# IO.net
KiCad netlist of a schematic drawn in Altium Designer
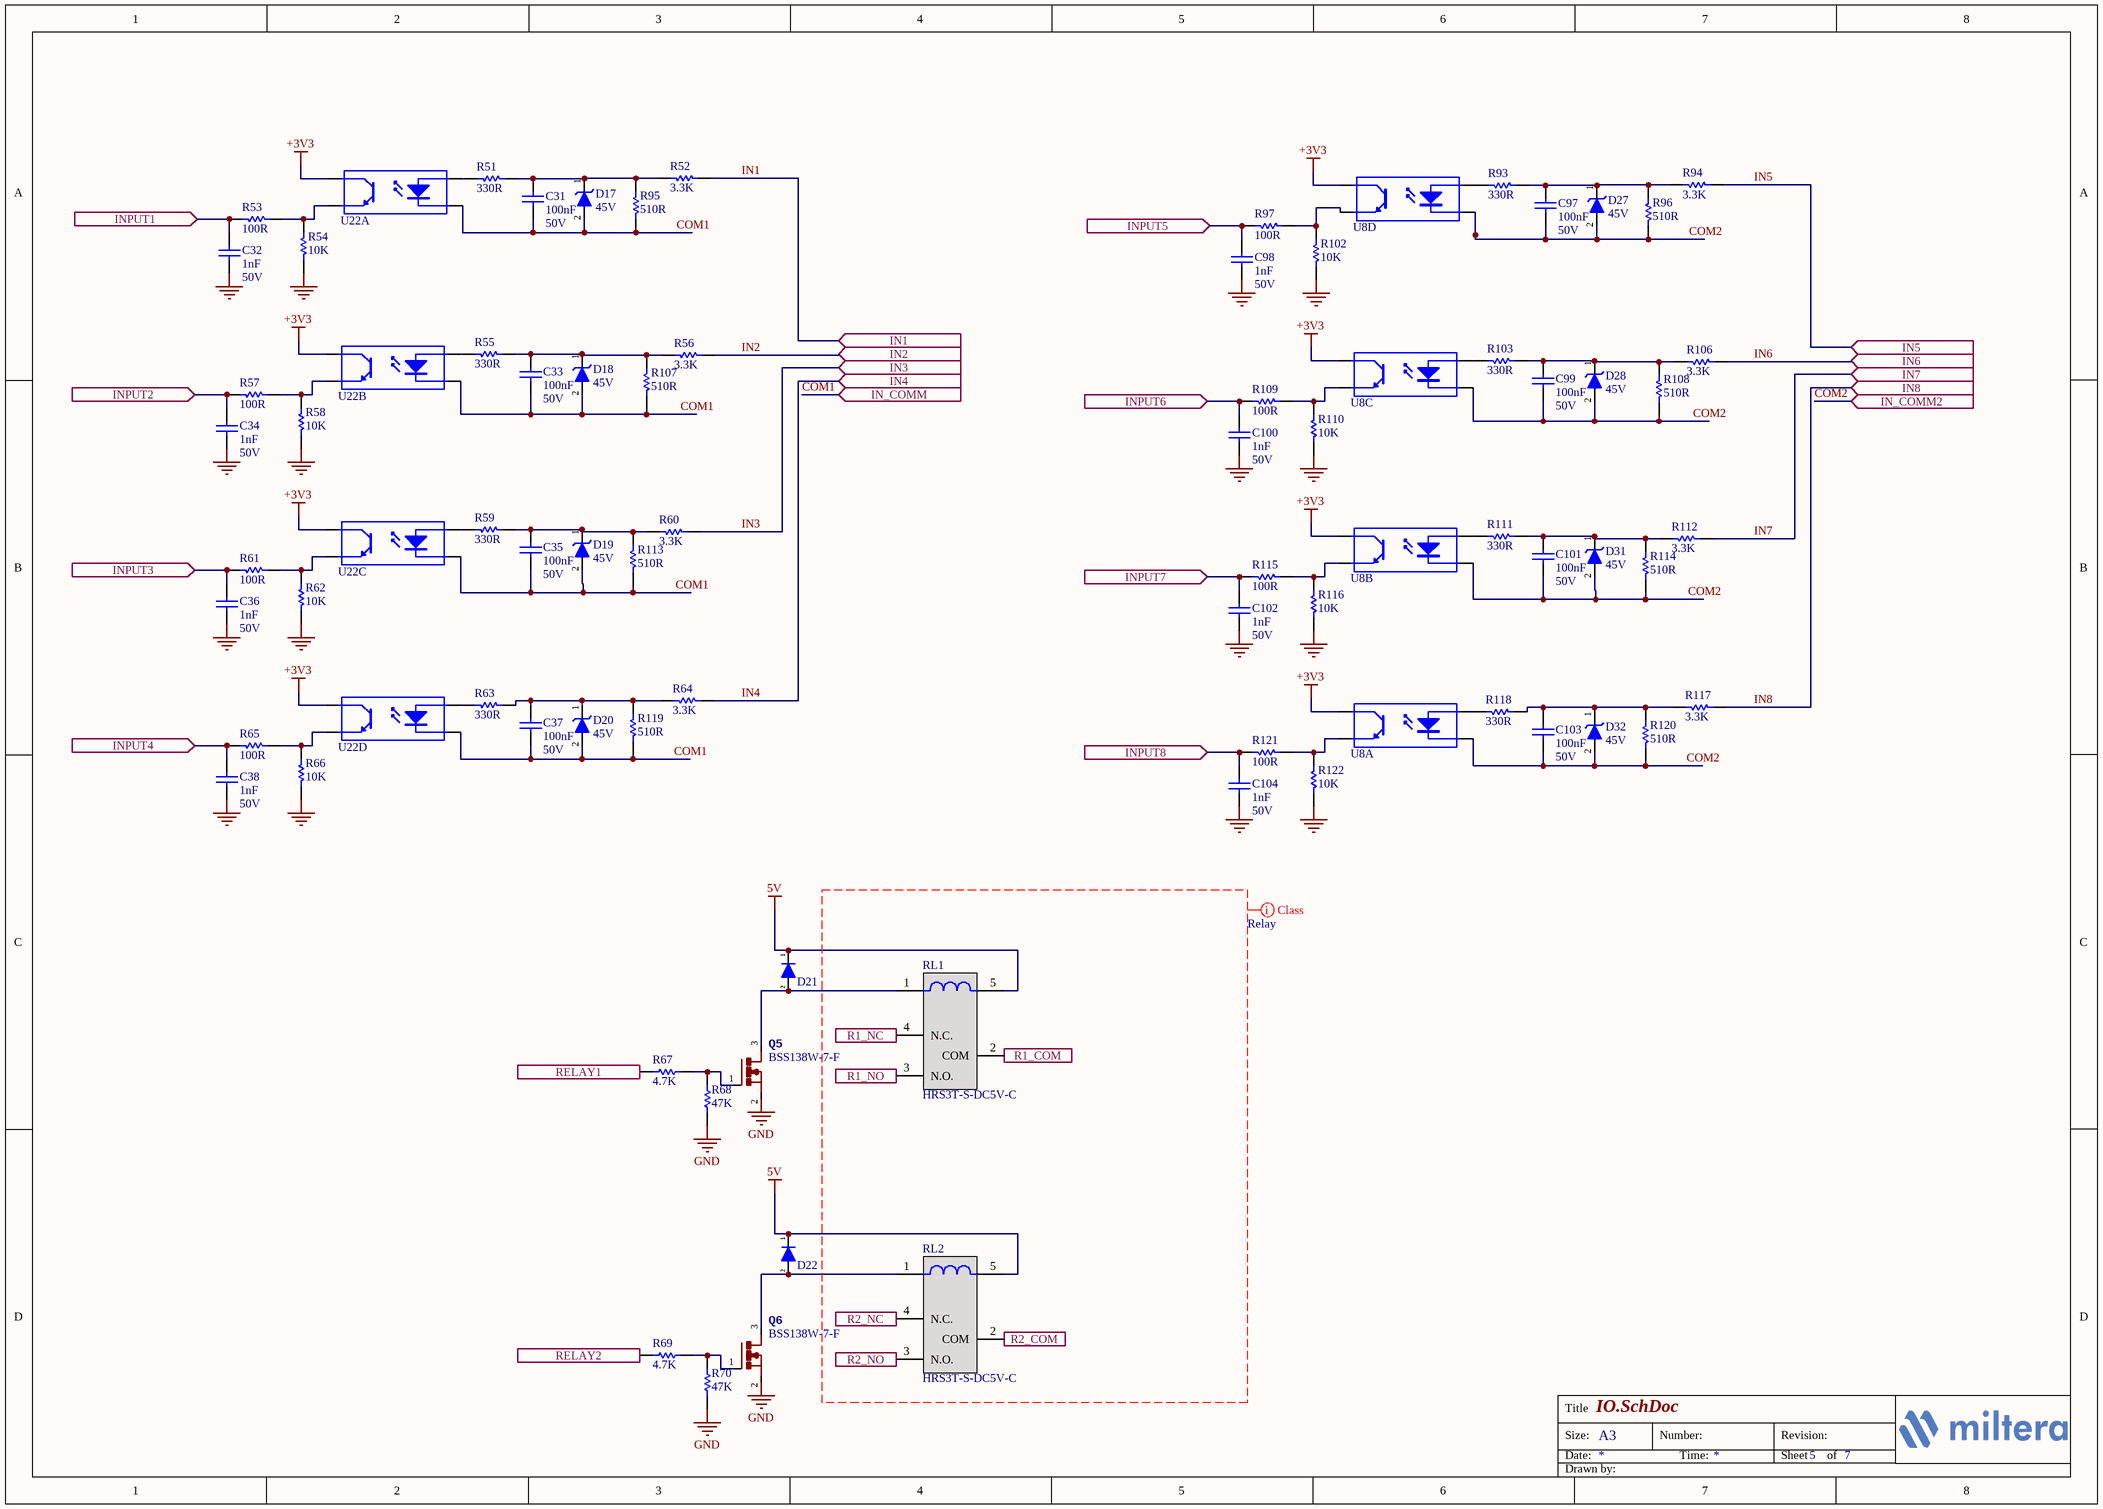
[diagram p0: IO.SchDoc]

(export (version "E")
  (design (tool "Eeschema 10.0.6"))
  (components
    (comp (ref "C31")
      (value "100nF")
      (footprint "CAP_0603")
      (description "CAP CER 100nF 50VDC %10 X7R SMD")
      (fields
        (field (name "VOLTAGE") "50V")
        (field (name "MANUFACTURER") "Samsung")
        (field (name "MANUFACTURER PART NUMBER") "CL10B104KB8NNNL")
      )
      (libsource (lib "open-components") (part "CAP"))
    )
    (comp (ref "C32")
      (value "1nF")
      (footprint "CAP_0603")
      (description "CAP CER 1nF 50VDC %10 X7R SMD")
      (fields
        (field (name "VOLTAGE") "50V")
        (field (name "MANUFACTURER") "Samsung")
        (field (name "MANUFACTURER PART NUMBER") "CL10B102KB8NNNL")
      )
      (libsource (lib "open-components") (part "CAP"))
    )
    (comp (ref "C33")
      (value "100nF")
      (footprint "CAP_0603")
      (description "CAP CER 100nF 50VDC %10 X7R SMD")
      (fields
        (field (name "VOLTAGE") "50V")
        (field (name "MANUFACTURER") "Samsung")
        (field (name "MANUFACTURER PART NUMBER") "CL10B104KB8NNNL")
      )
      (libsource (lib "open-components") (part "CAP"))
    )
    (comp (ref "C34")
      (value "1nF")
      (footprint "CAP_0603")
      (description "CAP CER 1nF 50VDC %10 X7R SMD")
      (fields
        (field (name "VOLTAGE") "50V")
        (field (name "MANUFACTURER") "Samsung")
        (field (name "MANUFACTURER PART NUMBER") "CL10B102KB8NNNL")
      )
      (libsource (lib "open-components") (part "CAP"))
    )
    (comp (ref "C35")
      (value "100nF")
      (footprint "CAP_0603")
      (description "CAP CER 100nF 50VDC %10 X7R SMD")
      (fields
        (field (name "VOLTAGE") "50V")
        (field (name "MANUFACTURER") "Samsung")
        (field (name "MANUFACTURER PART NUMBER") "CL10B104KB8NNNL")
      )
      (libsource (lib "open-components") (part "CAP"))
    )
    (comp (ref "C36")
      (value "1nF")
      (footprint "CAP_0603")
      (description "CAP CER 1nF 50VDC %10 X7R SMD")
      (fields
        (field (name "VOLTAGE") "50V")
        (field (name "MANUFACTURER") "Samsung")
        (field (name "MANUFACTURER PART NUMBER") "CL10B102KB8NNNL")
      )
      (libsource (lib "open-components") (part "CAP"))
    )
    (comp (ref "C37")
      (value "100nF")
      (footprint "CAP_0603")
      (description "CAP CER 100nF 50VDC %10 X7R SMD")
      (fields
        (field (name "VOLTAGE") "50V")
        (field (name "MANUFACTURER") "Samsung")
        (field (name "MANUFACTURER PART NUMBER") "CL10B104KB8NNNL")
      )
      (libsource (lib "open-components") (part "CAP"))
    )
    (comp (ref "C38")
      (value "1nF")
      (footprint "CAP_0603")
      (description "CAP CER 1nF 50VDC %10 X7R SMD")
      (fields
        (field (name "VOLTAGE") "50V")
        (field (name "MANUFACTURER") "Samsung")
        (field (name "MANUFACTURER PART NUMBER") "CL10B102KB8NNNL")
      )
      (libsource (lib "open-components") (part "CAP"))
    )
    (comp (ref "C97")
      (value "100nF")
      (footprint "CAP_0603")
      (description "CAP CER 100nF 50VDC %10 X7R SMD")
      (fields
        (field (name "VOLTAGE") "50V")
        (field (name "MANUFACTURER") "Samsung")
        (field (name "MANUFACTURER PART NUMBER") "CL10B104KB8NNNL")
      )
      (libsource (lib "open-components") (part "CAP"))
    )
    (comp (ref "C98")
      (value "1nF")
      (footprint "CAP_0603")
      (description "CAP CER 1nF 50VDC %10 X7R SMD")
      (fields
        (field (name "VOLTAGE") "50V")
        (field (name "MANUFACTURER") "Samsung")
        (field (name "MANUFACTURER PART NUMBER") "CL10B102KB8NNNL")
      )
      (libsource (lib "open-components") (part "CAP"))
    )
    (comp (ref "C99")
      (value "100nF")
      (footprint "CAP_0603")
      (description "CAP CER 100nF 50VDC %10 X7R SMD")
      (fields
        (field (name "VOLTAGE") "50V")
        (field (name "MANUFACTURER") "Samsung")
        (field (name "MANUFACTURER PART NUMBER") "CL10B104KB8NNNL")
      )
      (libsource (lib "open-components") (part "CAP"))
    )
    (comp (ref "C100")
      (value "1nF")
      (footprint "CAP_0603")
      (description "CAP CER 1nF 50VDC %10 X7R SMD")
      (fields
        (field (name "VOLTAGE") "50V")
        (field (name "MANUFACTURER") "Samsung")
        (field (name "MANUFACTURER PART NUMBER") "CL10B102KB8NNNL")
      )
      (libsource (lib "open-components") (part "CAP"))
    )
    (comp (ref "C101")
      (value "100nF")
      (footprint "CAP_0603")
      (description "CAP CER 100nF 50VDC %10 X7R SMD")
      (fields
        (field (name "VOLTAGE") "50V")
        (field (name "MANUFACTURER") "Samsung")
        (field (name "MANUFACTURER PART NUMBER") "CL10B104KB8NNNL")
      )
      (libsource (lib "open-components") (part "CAP"))
    )
    (comp (ref "C102")
      (value "1nF")
      (footprint "CAP_0603")
      (description "CAP CER 1nF 50VDC %10 X7R SMD")
      (fields
        (field (name "VOLTAGE") "50V")
        (field (name "MANUFACTURER") "Samsung")
        (field (name "MANUFACTURER PART NUMBER") "CL10B102KB8NNNL")
      )
      (libsource (lib "open-components") (part "CAP"))
    )
    (comp (ref "C103")
      (value "100nF")
      (footprint "CAP_0603")
      (description "CAP CER 100nF 50VDC %10 X7R SMD")
      (fields
        (field (name "VOLTAGE") "50V")
        (field (name "MANUFACTURER") "Samsung")
        (field (name "MANUFACTURER PART NUMBER") "CL10B104KB8NNNL")
      )
      (libsource (lib "open-components") (part "CAP"))
    )
    (comp (ref "C104")
      (value "1nF")
      (footprint "CAP_0603")
      (description "CAP CER 1nF 50VDC %10 X7R SMD")
      (fields
        (field (name "VOLTAGE") "50V")
        (field (name "MANUFACTURER") "Samsung")
        (field (name "MANUFACTURER PART NUMBER") "CL10B102KB8NNNL")
      )
      (libsource (lib "open-components") (part "CAP"))
    )
    (comp (ref "D17")
      (value "45V")
      (footprint "sod123w")
      (description "TVS DIODE 26VWM 42.1VC SOD123W")
      (fields
        (field (name "MANUFACTURER PART NUMBER") "PTVS26VS1UR,115")
        (field (name "MANUFACTURER") "Nexperia USA Inc.")
      )
      (libsource (lib "open-components") (part "ZENER-SMB"))
    )
    (comp (ref "D18")
      (value "45V")
      (footprint "sod123w")
      (description "TVS DIODE 26VWM 42.1VC SOD123W")
      (fields
        (field (name "MANUFACTURER PART NUMBER") "PTVS26VS1UR,115")
        (field (name "MANUFACTURER") "Nexperia USA Inc.")
      )
      (libsource (lib "open-components") (part "ZENER-SMB"))
    )
    (comp (ref "D19")
      (value "45V")
      (footprint "sod123w")
      (description "TVS DIODE 26VWM 42.1VC SOD123W")
      (fields
        (field (name "MANUFACTURER PART NUMBER") "PTVS26VS1UR,115")
        (field (name "MANUFACTURER") "Nexperia USA Inc.")
      )
      (libsource (lib "open-components") (part "ZENER-SMB"))
    )
    (comp (ref "D20")
      (value "45V")
      (footprint "sod123w")
      (description "TVS DIODE 26VWM 42.1VC SOD123W")
      (fields
        (field (name "MANUFACTURER PART NUMBER") "PTVS26VS1UR,115")
        (field (name "MANUFACTURER") "Nexperia USA Inc.")
      )
      (libsource (lib "open-components") (part "ZENER-SMB"))
    )
    (comp (ref "D21")
      (value "Diode-SMA")
      (footprint "SOD-123")
      (description "DIODE SCHOTTKY 350MA 40V SOD123")
      (fields (field (name "MANUFACTURER PART NUMBER") "SD103AW-HT") (field (name "MANUFACTURER") "HOTTECH"))
      (libsource (lib "open-components") (part "Diode-SMA"))
    )
    (comp (ref "D22")
      (value "Diode-SMA")
      (footprint "SOD-123")
      (description "DIODE SCHOTTKY 350MA 40V SOD123")
      (fields (field (name "MANUFACTURER PART NUMBER") "SD103AW-HT") (field (name "MANUFACTURER") "HOTTECH"))
      (libsource (lib "open-components") (part "Diode-SMA"))
    )
    (comp (ref "D27")
      (value "45V")
      (footprint "sod123w")
      (description "TVS DIODE 26VWM 42.1VC SOD123W")
      (fields
        (field (name "MANUFACTURER PART NUMBER") "PTVS26VS1UR,115")
        (field (name "MANUFACTURER") "Nexperia USA Inc.")
      )
      (libsource (lib "open-components") (part "ZENER-SMB"))
    )
    (comp (ref "D28")
      (value "45V")
      (footprint "sod123w")
      (description "TVS DIODE 26VWM 42.1VC SOD123W")
      (fields
        (field (name "MANUFACTURER PART NUMBER") "PTVS26VS1UR,115")
        (field (name "MANUFACTURER") "Nexperia USA Inc.")
      )
      (libsource (lib "open-components") (part "ZENER-SMB"))
    )
    (comp (ref "D31")
      (value "45V")
      (footprint "sod123w")
      (description "TVS DIODE 26VWM 42.1VC SOD123W")
      (fields
        (field (name "MANUFACTURER PART NUMBER") "PTVS26VS1UR,115")
        (field (name "MANUFACTURER") "Nexperia USA Inc.")
      )
      (libsource (lib "open-components") (part "ZENER-SMB"))
    )
    (comp (ref "D32")
      (value "45V")
      (footprint "sod123w")
      (description "TVS DIODE 26VWM 42.1VC SOD123W")
      (fields
        (field (name "MANUFACTURER PART NUMBER") "PTVS26VS1UR,115")
        (field (name "MANUFACTURER") "Nexperia USA Inc.")
      )
      (libsource (lib "open-components") (part "ZENER-SMB"))
    )
    (comp (ref "Q5")
      (value "MOSFET_N_GSD")
      (footprint "SOT323")
      (description "MOSFET N-CH 50V 200MA SC70-3")
      (fields
        (field (name "MANUFACTURER PART NUMBER") "BSS138W-7-F")
        (field (name "MANUFACTURER") "Diodes Incorporated")
      )
      (libsource (lib "open-components") (part "MOSFET_N_GSD"))
    )
    (comp (ref "Q6")
      (value "MOSFET_N_GSD")
      (footprint "SOT323")
      (description "MOSFET N-CH 50V 200MA SC70-3")
      (fields
        (field (name "MANUFACTURER PART NUMBER") "BSS138W-7-F")
        (field (name "MANUFACTURER") "Diodes Incorporated")
      )
      (libsource (lib "open-components") (part "MOSFET_N_GSD"))
    )
    (comp (ref "R51")
      (value "330R")
      (footprint "RES_0603")
      (description "RES 0603 330 Ohms 1% 1/10W-S 100PPM")
      (fields
        (field (name "MANUFACTURER") "ROYALOHM")
        (field (name "MANUFACTURER PART NUMBER") "0603SAF3300T5E")
      )
      (libsource (lib "open-components") (part "RES"))
    )
    (comp (ref "R52")
      (value "3.3K")
      (footprint "R1206")
      (description "RES.(3216) 1206 3.3K Ohms 1% 1/4W-S 100PPM")
      (fields
        (field (name "MANUFACTURER") "ROYALOHM")
        (field (name "MANUFACTURER PART NUMBER") "1206S4F3301T5E")
      )
      (libsource (lib "open-components") (part "RES"))
    )
    (comp (ref "R53")
      (value "100R")
      (footprint "RES_0603")
      (description "RES 0603 100 Ohms 1% 1/10W-S 100PPM")
      (fields
        (field (name "MANUFACTURER") "ROYALOHM")
        (field (name "MANUFACTURER PART NUMBER") "0603SAF1000T5E")
      )
      (libsource (lib "open-components") (part "RES"))
    )
    (comp (ref "R54")
      (value "10K")
      (footprint "RES_0603")
      (description "RES 0603 10k Ohms %1 1/10W 100PPM")
      (fields
        (field (name "MANUFACTURER") "ROYALOHM")
        (field (name "MANUFACTURER PART NUMBER") "0603SAF1002T5E")
      )
      (libsource (lib "open-components") (part "RES"))
    )
    (comp (ref "R55")
      (value "330R")
      (footprint "RES_0603")
      (description "RES 0603 330 Ohms 1% 1/10W-S 100PPM")
      (fields
        (field (name "MANUFACTURER") "ROYALOHM")
        (field (name "MANUFACTURER PART NUMBER") "0603SAF3300T5E")
      )
      (libsource (lib "open-components") (part "RES"))
    )
    (comp (ref "R56")
      (value "3.3K")
      (footprint "R1206")
      (description "RES.(3216) 1206 3.3K Ohms 1% 1/4W-S 100PPM")
      (fields
        (field (name "MANUFACTURER") "ROYALOHM")
        (field (name "MANUFACTURER PART NUMBER") "1206S4F3301T5E")
      )
      (libsource (lib "open-components") (part "RES"))
    )
    (comp (ref "R57")
      (value "100R")
      (footprint "RES_0603")
      (description "RES 0603 100 Ohms 1% 1/10W-S 100PPM")
      (fields
        (field (name "MANUFACTURER") "ROYALOHM")
        (field (name "MANUFACTURER PART NUMBER") "0603SAF1000T5E")
      )
      (libsource (lib "open-components") (part "RES"))
    )
    (comp (ref "R58")
      (value "10K")
      (footprint "RES_0603")
      (description "RES 0603 10k Ohms %1 1/10W 100PPM")
      (fields
        (field (name "MANUFACTURER") "ROYALOHM")
        (field (name "MANUFACTURER PART NUMBER") "0603SAF1002T5E")
      )
      (libsource (lib "open-components") (part "RES"))
    )
    (comp (ref "R59")
      (value "330R")
      (footprint "RES_0603")
      (description "RES 0603 330 Ohms 1% 1/10W-S 100PPM")
      (fields
        (field (name "MANUFACTURER") "ROYALOHM")
        (field (name "MANUFACTURER PART NUMBER") "0603SAF3300T5E")
      )
      (libsource (lib "open-components") (part "RES"))
    )
    (comp (ref "R60")
      (value "3.3K")
      (footprint "R1206")
      (description "RES.(3216) 1206 3.3K Ohms 1% 1/4W-S 100PPM")
      (fields
        (field (name "MANUFACTURER") "ROYALOHM")
        (field (name "MANUFACTURER PART NUMBER") "1206S4F3301T5E")
      )
      (libsource (lib "open-components") (part "RES"))
    )
    (comp (ref "R61")
      (value "100R")
      (footprint "RES_0603")
      (description "RES 0603 100 Ohms 1% 1/10W-S 100PPM")
      (fields
        (field (name "MANUFACTURER") "ROYALOHM")
        (field (name "MANUFACTURER PART NUMBER") "0603SAF1000T5E")
      )
      (libsource (lib "open-components") (part "RES"))
    )
    (comp (ref "R62")
      (value "10K")
      (footprint "RES_0603")
      (description "RES 0603 10k Ohms %1 1/10W 100PPM")
      (fields
        (field (name "MANUFACTURER") "ROYALOHM")
        (field (name "MANUFACTURER PART NUMBER") "0603SAF1002T5E")
      )
      (libsource (lib "open-components") (part "RES"))
    )
    (comp (ref "R63")
      (value "330R")
      (footprint "RES_0603")
      (description "RES 0603 330 Ohms 1% 1/10W-S 100PPM")
      (fields
        (field (name "MANUFACTURER") "ROYALOHM")
        (field (name "MANUFACTURER PART NUMBER") "0603SAF3300T5E")
      )
      (libsource (lib "open-components") (part "RES"))
    )
    (comp (ref "R64")
      (value "3.3K")
      (footprint "R1206")
      (description "RES.(3216) 1206 3.3K Ohms 1% 1/4W-S 100PPM")
      (fields
        (field (name "MANUFACTURER") "ROYALOHM")
        (field (name "MANUFACTURER PART NUMBER") "1206S4F3301T5E")
      )
      (libsource (lib "open-components") (part "RES"))
    )
    (comp (ref "R65")
      (value "100R")
      (footprint "RES_0603")
      (description "RES 0603 100 Ohms 1% 1/10W-S 100PPM")
      (fields
        (field (name "MANUFACTURER") "ROYALOHM")
        (field (name "MANUFACTURER PART NUMBER") "0603SAF1000T5E")
      )
      (libsource (lib "open-components") (part "RES"))
    )
    (comp (ref "R66")
      (value "10K")
      (footprint "RES_0603")
      (description "RES 0603 10k Ohms %1 1/10W 100PPM")
      (fields
        (field (name "MANUFACTURER") "ROYALOHM")
        (field (name "MANUFACTURER PART NUMBER") "0603SAF1002T5E")
      )
      (libsource (lib "open-components") (part "RES"))
    )
    (comp (ref "R67")
      (value "4.7K")
      (footprint "RES_0603")
      (description "RES 0603 4.7k Ohms %1 1/10W 100PPM")
      (fields
        (field (name "MANUFACTURER") "ROYALOHM")
        (field (name "MANUFACTURER PART NUMBER") "0603SAF4701T5E")
      )
      (libsource (lib "open-components") (part "RES"))
    )
    (comp (ref "R68")
      (value "47K")
      (footprint "RES_0603")
      (description "RES 0603 47K Ohms 1% 1/10W-S 100PPM")
      (fields
        (field (name "MANUFACTURER") "ROYALOHM")
        (field (name "MANUFACTURER PART NUMBER") "0603SAF4702T5E")
      )
      (libsource (lib "open-components") (part "RES"))
    )
    (comp (ref "R69")
      (value "4.7K")
      (footprint "RES_0603")
      (description "RES 0603 4.7k Ohms %1 1/10W 100PPM")
      (fields
        (field (name "MANUFACTURER") "ROYALOHM")
        (field (name "MANUFACTURER PART NUMBER") "0603SAF4701T5E")
      )
      (libsource (lib "open-components") (part "RES"))
    )
    (comp (ref "R70")
      (value "47K")
      (footprint "RES_0603")
      (description "RES 0603 47K Ohms 1% 1/10W-S 100PPM")
      (fields
        (field (name "MANUFACTURER") "ROYALOHM")
        (field (name "MANUFACTURER PART NUMBER") "0603SAF4702T5E")
      )
      (libsource (lib "open-components") (part "RES"))
    )
    (comp (ref "R93")
      (value "330R")
      (footprint "RES_0603")
      (description "RES 0603 330 Ohms 1% 1/10W-S 100PPM")
      (fields
        (field (name "MANUFACTURER") "ROYALOHM")
        (field (name "MANUFACTURER PART NUMBER") "0603SAF3300T5E")
      )
      (libsource (lib "open-components") (part "RES"))
    )
    (comp (ref "R94")
      (value "3.3K")
      (footprint "R1206")
      (description "RES.(3216) 1206 3.3K Ohms 1% 1/4W-S 100PPM")
      (fields
        (field (name "MANUFACTURER") "ROYALOHM")
        (field (name "MANUFACTURER PART NUMBER") "1206S4F3301T5E")
      )
      (libsource (lib "open-components") (part "RES"))
    )
    (comp (ref "R95")
      (value "510R")
      (footprint "R0603")
      (description "RES.(1608) 0603 510 Ohms 5% 1/10W-S 100PPM")
      (fields
        (field (name "MANUFACTURER") "ROYALOHM")
        (field (name "MANUFACTURER PART NUMBER") "0603SAJ0511T5E")
      )
      (libsource (lib "open-components") (part "RES"))
    )
    (comp (ref "R96")
      (value "510R")
      (footprint "R0603")
      (description "RES.(1608) 0603 510 Ohms 5% 1/10W-S 100PPM")
      (fields
        (field (name "MANUFACTURER") "ROYALOHM")
        (field (name "MANUFACTURER PART NUMBER") "0603SAJ0511T5E")
      )
      (libsource (lib "open-components") (part "RES"))
    )
    (comp (ref "R97")
      (value "100R")
      (footprint "RES_0603")
      (description "RES 0603 100 Ohms 1% 1/10W-S 100PPM")
      (fields
        (field (name "MANUFACTURER") "ROYALOHM")
        (field (name "MANUFACTURER PART NUMBER") "0603SAF1000T5E")
      )
      (libsource (lib "open-components") (part "RES"))
    )
    (comp (ref "R102")
      (value "10K")
      (footprint "RES_0603")
      (description "RES 0603 10k Ohms %1 1/10W 100PPM")
      (fields
        (field (name "MANUFACTURER") "ROYALOHM")
        (field (name "MANUFACTURER PART NUMBER") "0603SAF1002T5E")
      )
      (libsource (lib "open-components") (part "RES"))
    )
    (comp (ref "R103")
      (value "330R")
      (footprint "RES_0603")
      (description "RES 0603 330 Ohms 1% 1/10W-S 100PPM")
      (fields
        (field (name "MANUFACTURER") "ROYALOHM")
        (field (name "MANUFACTURER PART NUMBER") "0603SAF3300T5E")
      )
      (libsource (lib "open-components") (part "RES"))
    )
    (comp (ref "R106")
      (value "3.3K")
      (footprint "R1206")
      (description "RES.(3216) 1206 3.3K Ohms 1% 1/4W-S 100PPM")
      (fields
        (field (name "MANUFACTURER") "ROYALOHM")
        (field (name "MANUFACTURER PART NUMBER") "1206S4F3301T5E")
      )
      (libsource (lib "open-components") (part "RES"))
    )
    (comp (ref "R107")
      (value "510R")
      (footprint "R0603")
      (description "RES.(1608) 0603 510 Ohms 5% 1/10W-S 100PPM")
      (fields
        (field (name "MANUFACTURER") "ROYALOHM")
        (field (name "MANUFACTURER PART NUMBER") "0603SAJ0511T5E")
      )
      (libsource (lib "open-components") (part "RES"))
    )
    (comp (ref "R108")
      (value "510R")
      (footprint "R0603")
      (description "RES.(1608) 0603 510 Ohms 5% 1/10W-S 100PPM")
      (fields
        (field (name "MANUFACTURER") "ROYALOHM")
        (field (name "MANUFACTURER PART NUMBER") "0603SAJ0511T5E")
      )
      (libsource (lib "open-components") (part "RES"))
    )
    (comp (ref "R109")
      (value "100R")
      (footprint "RES_0603")
      (description "RES 0603 100 Ohms 1% 1/10W-S 100PPM")
      (fields
        (field (name "MANUFACTURER") "ROYALOHM")
        (field (name "MANUFACTURER PART NUMBER") "0603SAF1000T5E")
      )
      (libsource (lib "open-components") (part "RES"))
    )
    (comp (ref "R110")
      (value "10K")
      (footprint "RES_0603")
      (description "RES 0603 10k Ohms %1 1/10W 100PPM")
      (fields
        (field (name "MANUFACTURER") "ROYALOHM")
        (field (name "MANUFACTURER PART NUMBER") "0603SAF1002T5E")
      )
      (libsource (lib "open-components") (part "RES"))
    )
    (comp (ref "R111")
      (value "330R")
      (footprint "RES_0603")
      (description "RES 0603 330 Ohms 1% 1/10W-S 100PPM")
      (fields
        (field (name "MANUFACTURER") "ROYALOHM")
        (field (name "MANUFACTURER PART NUMBER") "0603SAF3300T5E")
      )
      (libsource (lib "open-components") (part "RES"))
    )
    (comp (ref "R112")
      (value "3.3K")
      (footprint "R1206")
      (description "RES.(3216) 1206 3.3K Ohms 1% 1/4W-S 100PPM")
      (fields
        (field (name "MANUFACTURER") "ROYALOHM")
        (field (name "MANUFACTURER PART NUMBER") "1206S4F3301T5E")
      )
      (libsource (lib "open-components") (part "RES"))
    )
    (comp (ref "R113")
      (value "510R")
      (footprint "R0603")
      (description "RES.(1608) 0603 510 Ohms 5% 1/10W-S 100PPM")
      (fields
        (field (name "MANUFACTURER") "ROYALOHM")
        (field (name "MANUFACTURER PART NUMBER") "0603SAJ0511T5E")
      )
      (libsource (lib "open-components") (part "RES"))
    )
    (comp (ref "R114")
      (value "510R")
      (footprint "R0603")
      (description "RES.(1608) 0603 510 Ohms 5% 1/10W-S 100PPM")
      (fields
        (field (name "MANUFACTURER") "ROYALOHM")
        (field (name "MANUFACTURER PART NUMBER") "0603SAJ0511T5E")
      )
      (libsource (lib "open-components") (part "RES"))
    )
    (comp (ref "R115")
      (value "100R")
      (footprint "RES_0603")
      (description "RES 0603 100 Ohms 1% 1/10W-S 100PPM")
      (fields
        (field (name "MANUFACTURER") "ROYALOHM")
        (field (name "MANUFACTURER PART NUMBER") "0603SAF1000T5E")
      )
      (libsource (lib "open-components") (part "RES"))
    )
    (comp (ref "R116")
      (value "10K")
      (footprint "RES_0603")
      (description "RES 0603 10k Ohms %1 1/10W 100PPM")
      (fields
        (field (name "MANUFACTURER") "ROYALOHM")
        (field (name "MANUFACTURER PART NUMBER") "0603SAF1002T5E")
      )
      (libsource (lib "open-components") (part "RES"))
    )
    (comp (ref "R117")
      (value "3.3K")
      (footprint "R1206")
      (description "RES.(3216) 1206 3.3K Ohms 1% 1/4W-S 100PPM")
      (fields
        (field (name "MANUFACTURER") "ROYALOHM")
        (field (name "MANUFACTURER PART NUMBER") "1206S4F3301T5E")
      )
      (libsource (lib "open-components") (part "RES"))
    )
    (comp (ref "R118")
      (value "330R")
      (footprint "RES_0603")
      (description "RES 0603 330 Ohms 1% 1/10W-S 100PPM")
      (fields
        (field (name "MANUFACTURER") "ROYALOHM")
        (field (name "MANUFACTURER PART NUMBER") "0603SAF3300T5E")
      )
      (libsource (lib "open-components") (part "RES"))
    )
    (comp (ref "R119")
      (value "510R")
      (footprint "R0603")
      (description "RES.(1608) 0603 510 Ohms 5% 1/10W-S 100PPM")
      (fields
        (field (name "MANUFACTURER") "ROYALOHM")
        (field (name "MANUFACTURER PART NUMBER") "0603SAJ0511T5E")
      )
      (libsource (lib "open-components") (part "RES"))
    )
    (comp (ref "R120")
      (value "510R")
      (footprint "R0603")
      (description "RES.(1608) 0603 510 Ohms 5% 1/10W-S 100PPM")
      (fields
        (field (name "MANUFACTURER") "ROYALOHM")
        (field (name "MANUFACTURER PART NUMBER") "0603SAJ0511T5E")
      )
      (libsource (lib "open-components") (part "RES"))
    )
    (comp (ref "R121")
      (value "100R")
      (footprint "RES_0603")
      (description "RES 0603 100 Ohms 1% 1/10W-S 100PPM")
      (fields
        (field (name "MANUFACTURER") "ROYALOHM")
        (field (name "MANUFACTURER PART NUMBER") "0603SAF1000T5E")
      )
      (libsource (lib "open-components") (part "RES"))
    )
    (comp (ref "R122")
      (value "10K")
      (footprint "RES_0603")
      (description "RES 0603 10k Ohms %1 1/10W 100PPM")
      (fields
        (field (name "MANUFACTURER") "ROYALOHM")
        (field (name "MANUFACTURER PART NUMBER") "0603SAF1002T5E")
      )
      (libsource (lib "open-components") (part "RES"))
    )
    (comp (ref "RL1")
      (value "HRS3T-S-DC5V-C")
      (footprint "SamacSys:JQ15VF")
      (description "RELAY POWER 10A 5VDC 1FormC HKE")
      (fields (field (name "MANUFACTURER") "HKE"))
      (libsource (lib "MTOSOS_R02") (part "HRS3T-S-DC5V-C"))
    )
    (comp (ref "RL2")
      (value "HRS3T-S-DC5V-C")
      (footprint "SamacSys:JQ15VF")
      (description "RELAY POWER 10A 5VDC 1FormC HKE")
      (fields (field (name "MANUFACTURER") "HKE"))
      (libsource (lib "MTOSOS_R02") (part "HRS3T-S-DC5V-C"))
    )
    (comp (ref "U8")
      (value "SFH6916")
      (footprint "SOIC-16")
      (description "OPTOISOLATOR TRANSISTOR OUTPUT 3.75KV 4CH SOP-16")
      (fields (field (name "MANUFACTURER") "VISHAY"))
      (libsource (lib "") (part "SFH6916_2"))
    )
    (comp (ref "U22")
      (value "SFH6916")
      (footprint "SOIC-16")
      (description "OPTOISOLATOR TRANSISTOR OUTPUT 3.75KV 4CH SOP-16")
      (fields (field (name "MANUFACTURER") "VISHAY"))
      (libsource (lib "DIO_1608SI_R06") (part "SFH6916"))
    )
  )
  (nets
    (net (code "1") (name "+3V3") (class "Default")
      (node (ref "U22") (pin "10") (pinfunction "C_10") (pintype "passive"))
      (node (ref "U22") (pin "12") (pinfunction "C_12") (pintype "passive"))
      (node (ref "U22") (pin "14") (pinfunction "C_14") (pintype "passive"))
      (node (ref "U22") (pin "16") (pinfunction "C_16") (pintype "passive"))
      (node (ref "U8") (pin "10") (pinfunction "C_10") (pintype "passive"))
      (node (ref "U8") (pin "12") (pinfunction "C_12") (pintype "passive"))
      (node (ref "U8") (pin "14") (pinfunction "C_14") (pintype "passive"))
      (node (ref "U8") (pin "16") (pinfunction "C_16") (pintype "passive"))
    )
    (net (code "2") (name "/COM1") (class "Default")
      (node (ref "C31") (pin "2") (pinfunction "2_2") (pintype "passive"))
      (node (ref "C33") (pin "2") (pinfunction "2_2") (pintype "passive"))
      (node (ref "C35") (pin "2") (pinfunction "2_2") (pintype "passive"))
      (node (ref "C37") (pin "2") (pinfunction "2_2") (pintype "passive"))
      (node (ref "D17") (pin "2") (pinfunction "A_2") (pintype "passive"))
      (node (ref "D18") (pin "2") (pinfunction "A_2") (pintype "passive"))
      (node (ref "D19") (pin "2") (pinfunction "A_2") (pintype "passive"))
      (node (ref "D20") (pin "2") (pinfunction "A_2") (pintype "passive"))
      (node (ref "R107") (pin "1") (pinfunction "1_1") (pintype "passive"))
      (node (ref "R113") (pin "1") (pinfunction "1_1") (pintype "passive"))
      (node (ref "R119") (pin "1") (pinfunction "1_1") (pintype "passive"))
      (node (ref "R95") (pin "1") (pinfunction "1_1") (pintype "passive"))
      (node (ref "U22") (pin "2") (pinfunction "K_2") (pintype "passive"))
      (node (ref "U22") (pin "4") (pinfunction "K_4") (pintype "passive"))
      (node (ref "U22") (pin "6") (pinfunction "K_6") (pintype "passive"))
      (node (ref "U22") (pin "8") (pinfunction "K_8") (pintype "passive"))
    )
    (net (code "3") (name "/COM2") (class "Default")
      (node (ref "C101") (pin "2") (pinfunction "2_2") (pintype "passive"))
      (node (ref "C103") (pin "2") (pinfunction "2_2") (pintype "passive"))
      (node (ref "C97") (pin "2") (pinfunction "2_2") (pintype "passive"))
      (node (ref "C99") (pin "2") (pinfunction "2_2") (pintype "passive"))
      (node (ref "D27") (pin "2") (pinfunction "A_2") (pintype "passive"))
      (node (ref "D28") (pin "2") (pinfunction "A_2") (pintype "passive"))
      (node (ref "D31") (pin "2") (pinfunction "A_2") (pintype "passive"))
      (node (ref "D32") (pin "2") (pinfunction "A_2") (pintype "passive"))
      (node (ref "R108") (pin "1") (pinfunction "1_1") (pintype "passive"))
      (node (ref "R114") (pin "1") (pinfunction "1_1") (pintype "passive"))
      (node (ref "R120") (pin "1") (pinfunction "1_1") (pintype "passive"))
      (node (ref "R96") (pin "1") (pinfunction "1_1") (pintype "passive"))
      (node (ref "U8") (pin "2") (pinfunction "K_2") (pintype "passive"))
      (node (ref "U8") (pin "4") (pinfunction "K_4") (pintype "passive"))
      (node (ref "U8") (pin "6") (pinfunction "K_6") (pintype "passive"))
      (node (ref "U8") (pin "8") (pinfunction "K_8") (pintype "passive"))
    )
    (net (code "4") (name "/IN1") (class "Default")
      (node (ref "R52") (pin "2") (pinfunction "2_2") (pintype "passive"))
    )
    (net (code "5") (name "/IN2") (class "Default")
      (node (ref "R56") (pin "2") (pinfunction "2_2") (pintype "passive"))
    )
    (net (code "6") (name "/IN3") (class "Default")
      (node (ref "R60") (pin "2") (pinfunction "2_2") (pintype "passive"))
    )
    (net (code "7") (name "/IN4") (class "Default")
      (node (ref "R64") (pin "2") (pinfunction "2_2") (pintype "passive"))
    )
    (net (code "8") (name "/IN5") (class "Default")
      (node (ref "R94") (pin "2") (pinfunction "2_2") (pintype "passive"))
    )
    (net (code "9") (name "/IN6") (class "Default")
      (node (ref "R106") (pin "2") (pinfunction "2_2") (pintype "passive"))
    )
    (net (code "10") (name "/IN7") (class "Default")
      (node (ref "R112") (pin "2") (pinfunction "2_2") (pintype "passive"))
    )
    (net (code "11") (name "/IN8") (class "Default")
      (node (ref "R117") (pin "2") (pinfunction "2_2") (pintype "passive"))
    )
    (net (code "12") (name "/INPUT1") (class "Default")
      (node (ref "C32") (pin "1") (pinfunction "1_1") (pintype "passive"))
      (node (ref "R53") (pin "2") (pinfunction "2_2") (pintype "passive"))
    )
    (net (code "13") (name "/INPUT2") (class "Default")
      (node (ref "C34") (pin "1") (pinfunction "1_1") (pintype "passive"))
      (node (ref "R57") (pin "2") (pinfunction "2_2") (pintype "passive"))
    )
    (net (code "14") (name "/INPUT3") (class "Default")
      (node (ref "C36") (pin "1") (pinfunction "1_1") (pintype "passive"))
      (node (ref "R61") (pin "2") (pinfunction "2_2") (pintype "passive"))
    )
    (net (code "15") (name "/INPUT4") (class "Default")
      (node (ref "C38") (pin "1") (pinfunction "1_1") (pintype "passive"))
      (node (ref "R65") (pin "2") (pinfunction "2_2") (pintype "passive"))
    )
    (net (code "16") (name "/INPUT5") (class "Default")
      (node (ref "C98") (pin "1") (pinfunction "1_1") (pintype "passive"))
      (node (ref "R97") (pin "2") (pinfunction "2_2") (pintype "passive"))
    )
    (net (code "17") (name "/INPUT6") (class "Default")
      (node (ref "C100") (pin "1") (pinfunction "1_1") (pintype "passive"))
      (node (ref "R109") (pin "2") (pinfunction "2_2") (pintype "passive"))
    )
    (net (code "18") (name "/INPUT7") (class "Default")
      (node (ref "C102") (pin "1") (pinfunction "1_1") (pintype "passive"))
      (node (ref "R115") (pin "2") (pinfunction "2_2") (pintype "passive"))
    )
    (net (code "19") (name "/INPUT8") (class "Default")
      (node (ref "C104") (pin "1") (pinfunction "1_1") (pintype "passive"))
      (node (ref "R121") (pin "2") (pinfunction "2_2") (pintype "passive"))
    )
    (net (code "20") (name "/R1_COM") (class "Default")
      (node (ref "RL1") (pin "2") (pinfunction "COM_2") (pintype "passive"))
    )
    (net (code "21") (name "/R1_NC") (class "Default")
      (node (ref "RL1") (pin "4") (pinfunction "N.C._4") (pintype "passive"))
    )
    (net (code "22") (name "/R1_NO") (class "Default")
      (node (ref "RL1") (pin "3") (pinfunction "N.O._3") (pintype "passive"))
    )
    (net (code "23") (name "/R2_COM") (class "Default")
      (node (ref "RL2") (pin "2") (pinfunction "COM_2") (pintype "passive"))
    )
    (net (code "24") (name "/R2_NC") (class "Default")
      (node (ref "RL2") (pin "4") (pinfunction "N.C._4") (pintype "passive"))
    )
    (net (code "25") (name "/R2_NO") (class "Default")
      (node (ref "RL2") (pin "3") (pinfunction "N.O._3") (pintype "passive"))
    )
    (net (code "26") (name "/RELAY1") (class "Default")
      (node (ref "R67") (pin "1") (pinfunction "1_1") (pintype "passive"))
    )
    (net (code "27") (name "/RELAY2") (class "Default")
      (node (ref "R69") (pin "1") (pinfunction "1_1") (pintype "passive"))
    )
    (net (code "28") (name "5V") (class "Default")
      (node (ref "D21") (pin "1") (pinfunction "1_1") (pintype "passive"))
      (node (ref "D22") (pin "1") (pinfunction "1_1") (pintype "passive"))
      (node (ref "RL1") (pin "5") (pinfunction "COIL_2_5") (pintype "passive"))
      (node (ref "RL2") (pin "5") (pinfunction "COIL_2_5") (pintype "passive"))
    )
    (net (code "29") (name "GND") (class "Default")
      (node (ref "C100") (pin "2") (pinfunction "2_2") (pintype "passive"))
      (node (ref "C102") (pin "2") (pinfunction "2_2") (pintype "passive"))
      (node (ref "C104") (pin "2") (pinfunction "2_2") (pintype "passive"))
      (node (ref "C32") (pin "2") (pinfunction "2_2") (pintype "passive"))
      (node (ref "C34") (pin "2") (pinfunction "2_2") (pintype "passive"))
      (node (ref "C36") (pin "2") (pinfunction "2_2") (pintype "passive"))
      (node (ref "C38") (pin "2") (pinfunction "2_2") (pintype "passive"))
      (node (ref "C98") (pin "2") (pinfunction "2_2") (pintype "passive"))
      (node (ref "Q5") (pin "2") (pinfunction "S_2") (pintype "passive"))
      (node (ref "Q6") (pin "2") (pinfunction "S_2") (pintype "passive"))
      (node (ref "R102") (pin "2") (pinfunction "2_2") (pintype "passive"))
      (node (ref "R110") (pin "2") (pinfunction "2_2") (pintype "passive"))
      (node (ref "R116") (pin "2") (pinfunction "2_2") (pintype "passive"))
      (node (ref "R122") (pin "2") (pinfunction "2_2") (pintype "passive"))
      (node (ref "R54") (pin "2") (pinfunction "2_2") (pintype "passive"))
      (node (ref "R58") (pin "2") (pinfunction "2_2") (pintype "passive"))
      (node (ref "R62") (pin "2") (pinfunction "2_2") (pintype "passive"))
      (node (ref "R66") (pin "2") (pinfunction "2_2") (pintype "passive"))
      (node (ref "R68") (pin "2") (pinfunction "2_2") (pintype "passive"))
      (node (ref "R70") (pin "2") (pinfunction "2_2") (pintype "passive"))
    )
    (net (code "30") (name "Net-(D17-K)") (class "Default")
      (node (ref "C31") (pin "1") (pinfunction "1_1") (pintype "passive"))
      (node (ref "D17") (pin "1") (pinfunction "K_1") (pintype "passive"))
      (node (ref "R51") (pin "1") (pinfunction "1_1") (pintype "passive"))
      (node (ref "R52") (pin "1") (pinfunction "1_1") (pintype "passive"))
      (node (ref "R95") (pin "2") (pinfunction "2_2") (pintype "passive"))
    )
    (net (code "31") (name "Net-(D18-K)") (class "Default")
      (node (ref "C33") (pin "1") (pinfunction "1_1") (pintype "passive"))
      (node (ref "D18") (pin "1") (pinfunction "K_1") (pintype "passive"))
      (node (ref "R107") (pin "2") (pinfunction "2_2") (pintype "passive"))
      (node (ref "R55") (pin "1") (pinfunction "1_1") (pintype "passive"))
      (node (ref "R56") (pin "1") (pinfunction "1_1") (pintype "passive"))
    )
    (net (code "32") (name "Net-(D19-K)") (class "Default")
      (node (ref "C35") (pin "1") (pinfunction "1_1") (pintype "passive"))
      (node (ref "D19") (pin "1") (pinfunction "K_1") (pintype "passive"))
      (node (ref "R113") (pin "2") (pinfunction "2_2") (pintype "passive"))
      (node (ref "R59") (pin "1") (pinfunction "1_1") (pintype "passive"))
      (node (ref "R60") (pin "1") (pinfunction "1_1") (pintype "passive"))
    )
    (net (code "33") (name "Net-(D20-K)") (class "Default")
      (node (ref "C37") (pin "1") (pinfunction "1_1") (pintype "passive"))
      (node (ref "D20") (pin "1") (pinfunction "K_1") (pintype "passive"))
      (node (ref "R119") (pin "2") (pinfunction "2_2") (pintype "passive"))
      (node (ref "R63") (pin "1") (pinfunction "1_1") (pintype "passive"))
      (node (ref "R64") (pin "1") (pinfunction "1_1") (pintype "passive"))
    )
    (net (code "34") (name "Net-(D27-K)") (class "Default")
      (node (ref "C97") (pin "1") (pinfunction "1_1") (pintype "passive"))
      (node (ref "D27") (pin "1") (pinfunction "K_1") (pintype "passive"))
      (node (ref "R93") (pin "1") (pinfunction "1_1") (pintype "passive"))
      (node (ref "R94") (pin "1") (pinfunction "1_1") (pintype "passive"))
      (node (ref "R96") (pin "2") (pinfunction "2_2") (pintype "passive"))
    )
    (net (code "35") (name "Net-(D28-K)") (class "Default")
      (node (ref "C99") (pin "1") (pinfunction "1_1") (pintype "passive"))
      (node (ref "D28") (pin "1") (pinfunction "K_1") (pintype "passive"))
      (node (ref "R103") (pin "1") (pinfunction "1_1") (pintype "passive"))
      (node (ref "R106") (pin "1") (pinfunction "1_1") (pintype "passive"))
      (node (ref "R108") (pin "2") (pinfunction "2_2") (pintype "passive"))
    )
    (net (code "36") (name "Net-(D31-K)") (class "Default")
      (node (ref "C101") (pin "1") (pinfunction "1_1") (pintype "passive"))
      (node (ref "D31") (pin "1") (pinfunction "K_1") (pintype "passive"))
      (node (ref "R111") (pin "1") (pinfunction "1_1") (pintype "passive"))
      (node (ref "R112") (pin "1") (pinfunction "1_1") (pintype "passive"))
      (node (ref "R114") (pin "2") (pinfunction "2_2") (pintype "passive"))
    )
    (net (code "37") (name "Net-(D32-K)") (class "Default")
      (node (ref "C103") (pin "1") (pinfunction "1_1") (pintype "passive"))
      (node (ref "D32") (pin "1") (pinfunction "K_1") (pintype "passive"))
      (node (ref "R117") (pin "1") (pinfunction "1_1") (pintype "passive"))
      (node (ref "R118") (pin "1") (pinfunction "1_1") (pintype "passive"))
      (node (ref "R120") (pin "2") (pinfunction "2_2") (pintype "passive"))
    )
    (net (code "38") (name "Net-(Q5-D)") (class "Default")
      (node (ref "D21") (pin "2") (pinfunction "2_2") (pintype "passive"))
      (node (ref "Q5") (pin "3") (pinfunction "D_3") (pintype "passive"))
      (node (ref "RL1") (pin "1") (pinfunction "COIL_1_1") (pintype "passive"))
    )
    (net (code "39") (name "Net-(Q5-G)") (class "Default")
      (node (ref "Q5") (pin "1") (pinfunction "G_1") (pintype "passive"))
      (node (ref "R67") (pin "2") (pinfunction "2_2") (pintype "passive"))
      (node (ref "R68") (pin "1") (pinfunction "1_1") (pintype "passive"))
    )
    (net (code "40") (name "Net-(Q6-D)") (class "Default")
      (node (ref "D22") (pin "2") (pinfunction "2_2") (pintype "passive"))
      (node (ref "Q6") (pin "3") (pinfunction "D_3") (pintype "passive"))
      (node (ref "RL2") (pin "1") (pinfunction "COIL_1_1") (pintype "passive"))
    )
    (net (code "41") (name "Net-(Q6-G)") (class "Default")
      (node (ref "Q6") (pin "1") (pinfunction "G_1") (pintype "passive"))
      (node (ref "R69") (pin "2") (pinfunction "2_2") (pintype "passive"))
      (node (ref "R70") (pin "1") (pinfunction "1_1") (pintype "passive"))
    )
    (net (code "42") (name "Net-(U8A-A)") (class "Default")
      (node (ref "R118") (pin "2") (pinfunction "2_2") (pintype "passive"))
      (node (ref "U8") (pin "1") (pinfunction "A_1") (pintype "passive"))
    )
    (net (code "43") (name "Net-(U8A-E)") (class "Default")
      (node (ref "R121") (pin "1") (pinfunction "1_1") (pintype "passive"))
      (node (ref "R122") (pin "1") (pinfunction "1_1") (pintype "passive"))
      (node (ref "U8") (pin "15") (pinfunction "E_15") (pintype "passive"))
    )
    (net (code "44") (name "Net-(U8B-A)") (class "Default")
      (node (ref "R111") (pin "2") (pinfunction "2_2") (pintype "passive"))
      (node (ref "U8") (pin "3") (pinfunction "A_3") (pintype "passive"))
    )
    (net (code "45") (name "Net-(U8B-E)") (class "Default")
      (node (ref "R115") (pin "1") (pinfunction "1_1") (pintype "passive"))
      (node (ref "R116") (pin "1") (pinfunction "1_1") (pintype "passive"))
      (node (ref "U8") (pin "13") (pinfunction "E_13") (pintype "passive"))
    )
    (net (code "46") (name "Net-(U8C-A)") (class "Default")
      (node (ref "R103") (pin "2") (pinfunction "2_2") (pintype "passive"))
      (node (ref "U8") (pin "5") (pinfunction "A_5") (pintype "passive"))
    )
    (net (code "47") (name "Net-(U8C-E)") (class "Default")
      (node (ref "R109") (pin "1") (pinfunction "1_1") (pintype "passive"))
      (node (ref "R110") (pin "1") (pinfunction "1_1") (pintype "passive"))
      (node (ref "U8") (pin "11") (pinfunction "E_11") (pintype "passive"))
    )
    (net (code "48") (name "Net-(U8D-A)") (class "Default")
      (node (ref "R93") (pin "2") (pinfunction "2_2") (pintype "passive"))
      (node (ref "U8") (pin "7") (pinfunction "A_7") (pintype "passive"))
    )
    (net (code "49") (name "Net-(U8D-E)") (class "Default")
      (node (ref "R102") (pin "1") (pinfunction "1_1") (pintype "passive"))
      (node (ref "R97") (pin "1") (pinfunction "1_1") (pintype "passive"))
      (node (ref "U8") (pin "9") (pinfunction "E_9") (pintype "passive"))
    )
    (net (code "50") (name "Net-(U22A-A)") (class "Default")
      (node (ref "R51") (pin "2") (pinfunction "2_2") (pintype "passive"))
      (node (ref "U22") (pin "1") (pinfunction "A_1") (pintype "passive"))
    )
    (net (code "51") (name "Net-(U22A-E)") (class "Default")
      (node (ref "R53") (pin "1") (pinfunction "1_1") (pintype "passive"))
      (node (ref "R54") (pin "1") (pinfunction "1_1") (pintype "passive"))
      (node (ref "U22") (pin "15") (pinfunction "E_15") (pintype "passive"))
    )
    (net (code "52") (name "Net-(U22B-A)") (class "Default")
      (node (ref "R55") (pin "2") (pinfunction "2_2") (pintype "passive"))
      (node (ref "U22") (pin "3") (pinfunction "A_3") (pintype "passive"))
    )
    (net (code "53") (name "Net-(U22B-E)") (class "Default")
      (node (ref "R57") (pin "1") (pinfunction "1_1") (pintype "passive"))
      (node (ref "R58") (pin "1") (pinfunction "1_1") (pintype "passive"))
      (node (ref "U22") (pin "13") (pinfunction "E_13") (pintype "passive"))
    )
    (net (code "54") (name "Net-(U22C-A)") (class "Default")
      (node (ref "R59") (pin "2") (pinfunction "2_2") (pintype "passive"))
      (node (ref "U22") (pin "5") (pinfunction "A_5") (pintype "passive"))
    )
    (net (code "55") (name "Net-(U22C-E)") (class "Default")
      (node (ref "R61") (pin "1") (pinfunction "1_1") (pintype "passive"))
      (node (ref "R62") (pin "1") (pinfunction "1_1") (pintype "passive"))
      (node (ref "U22") (pin "11") (pinfunction "E_11") (pintype "passive"))
    )
    (net (code "56") (name "Net-(U22D-A)") (class "Default")
      (node (ref "R63") (pin "2") (pinfunction "2_2") (pintype "passive"))
      (node (ref "U22") (pin "7") (pinfunction "A_7") (pintype "passive"))
    )
    (net (code "57") (name "Net-(U22D-E)") (class "Default")
      (node (ref "R65") (pin "1") (pinfunction "1_1") (pintype "passive"))
      (node (ref "R66") (pin "1") (pinfunction "1_1") (pintype "passive"))
      (node (ref "U22") (pin "9") (pinfunction "E_9") (pintype "passive"))
    )
  )
)
